# MKXdbV2_ModConn.net
KiCad netlist of a schematic drawn in Altium Designer
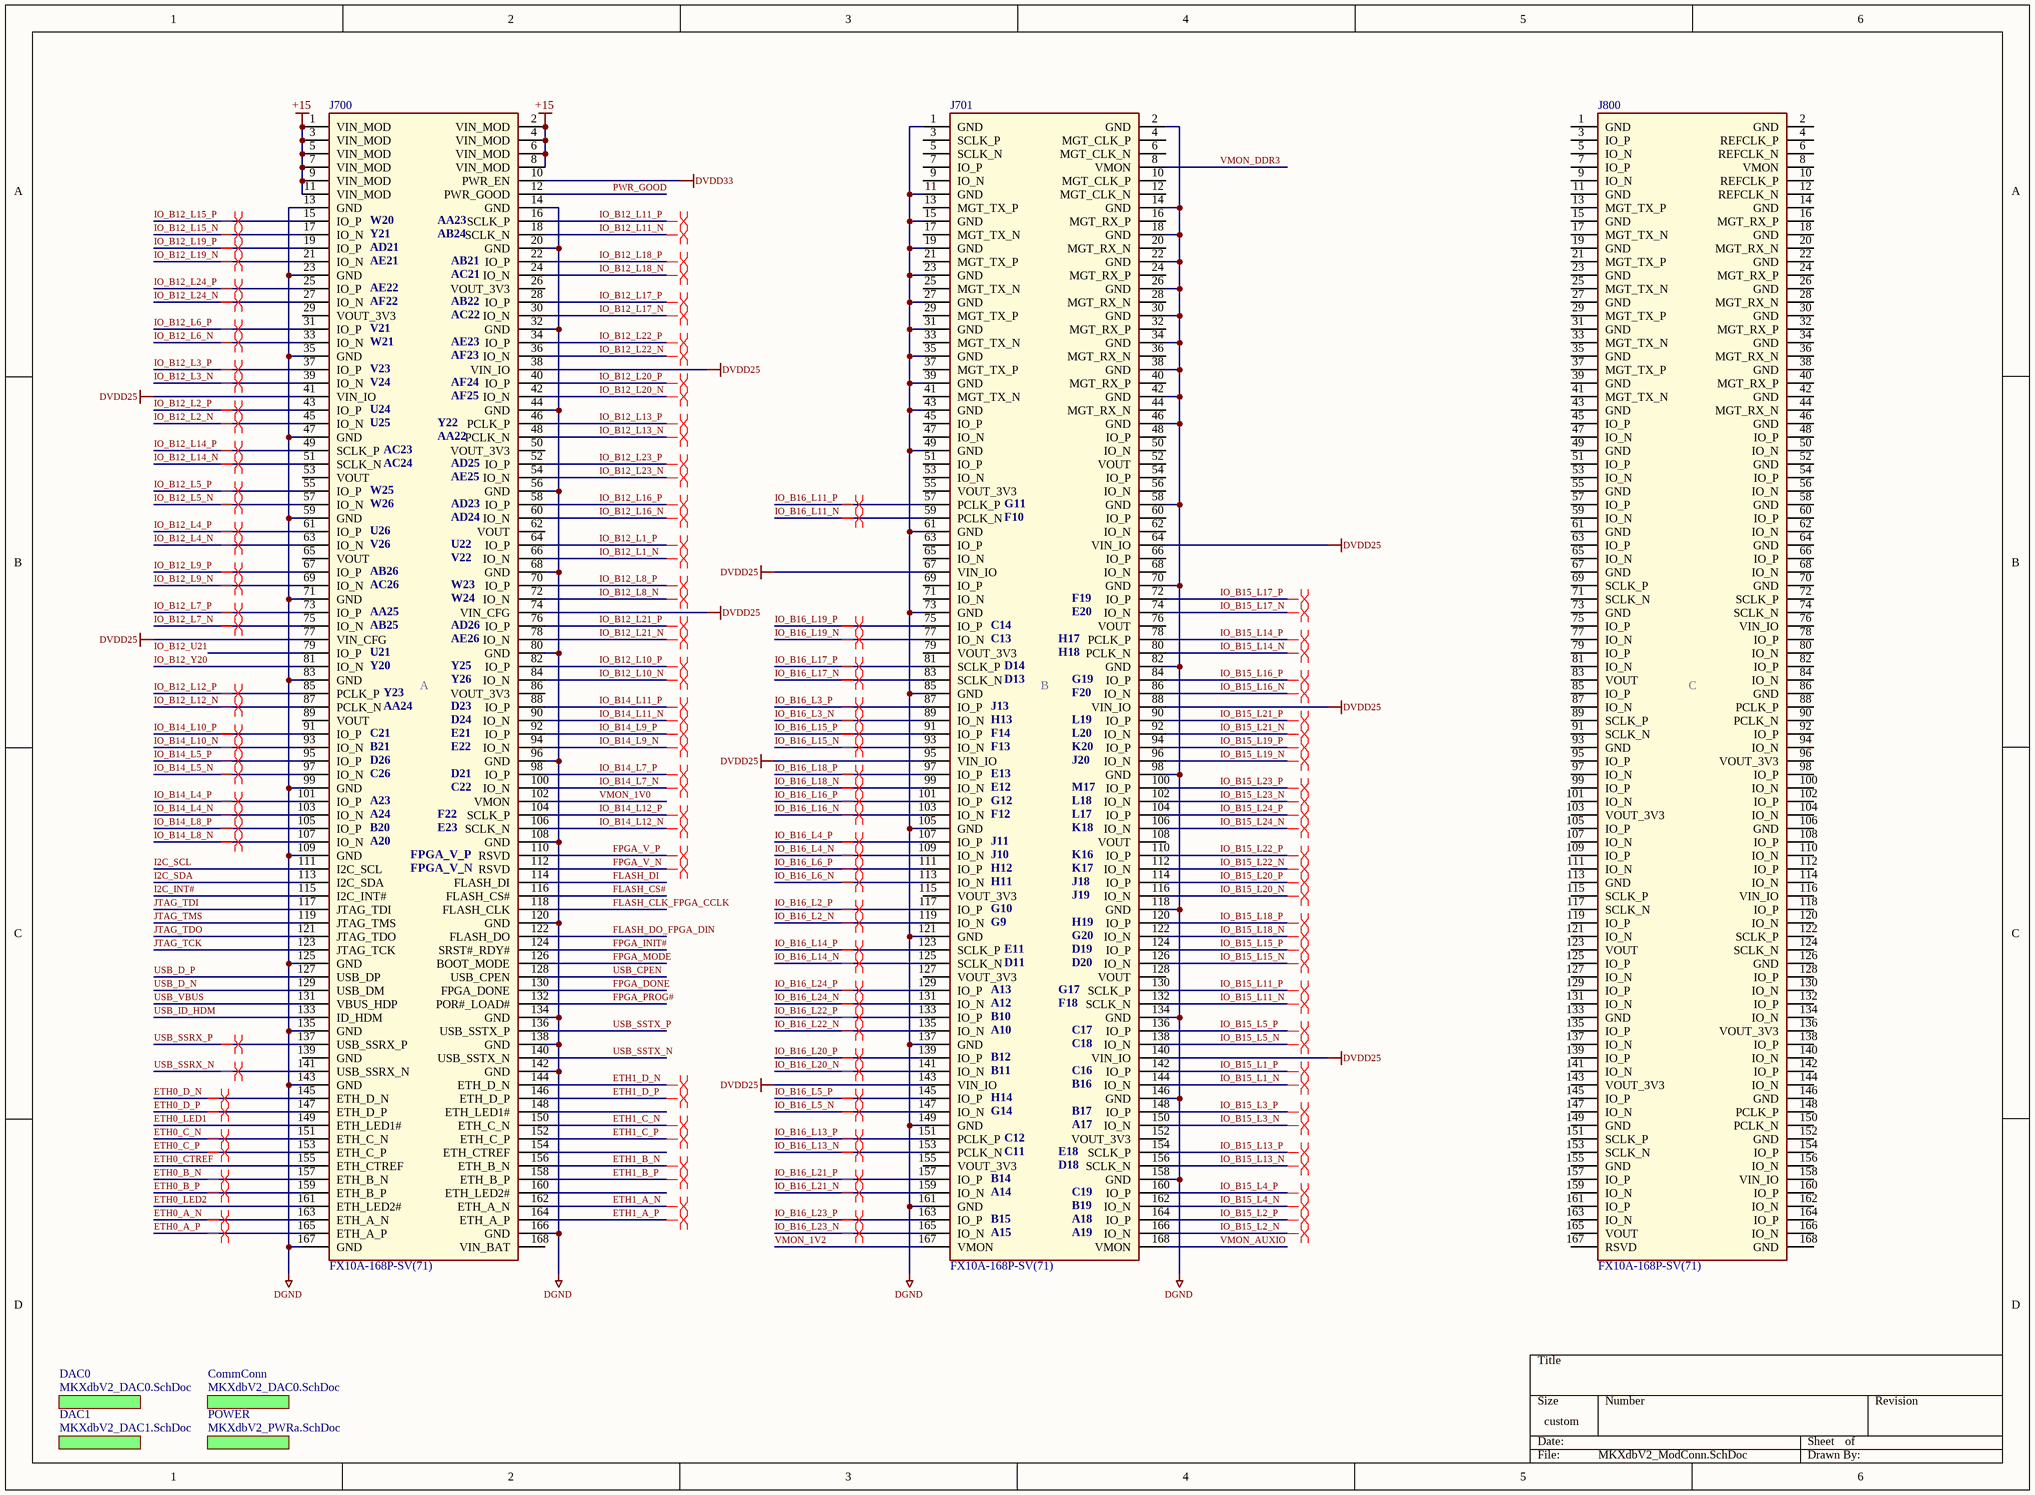
[diagram p0: MKXdbV2_ModConn.SchDoc]

(export (version "E")
  (design (tool "Eeschema 10.0.6"))
  (components
    (comp (ref "J700")
      (value "FX10A-168P-SV(71)")
      (footprint "Mercury_Baseboard_Connector")
      (description "Mercury Baseboard Connector")
      (fields
        (field (name "MANUFACTURER") "Hirose")
        (field (name "DISTPARTNUMBER") "FX10A-168P-SV(71)-ND")
        (field (name "CHECK SCH") "CG_2015-03-03")
      )
      (libsource (lib "Enclustra-Mars-Mercury-Altium-Library") (part "Mercury_Baseboard_Connector-A"))
    )
    (comp (ref "J701")
      (value "FX10A-168P-SV(71)")
      (footprint "Mercury_Baseboard_Connector")
      (description "Mercury Baseboard Connector")
      (fields
        (field (name "MANUFACTURER") "Hirose")
        (field (name "DISTPARTNUMBER") "FX10A-168P-SV(71)-ND")
        (field (name "CHECK SCH") "CG_2015-03-03")
      )
      (libsource (lib "Enclustra-Mars-Mercury-Altium-Library") (part "Mercury_Baseboard_Connector-B"))
    )
    (comp (ref "J800")
      (value "FX10A-168P-SV(71)")
      (footprint "Mercury_Baseboard_Connector")
      (description "Mercury Baseboard Connector")
      (fields
        (field (name "MANUFACTURER") "Hirose")
        (field (name "DISTPARTNUMBER") "FX10A-168P-SV(71)-ND")
        (field (name "CHECK SCH") "CG_2015-03-03")
      )
      (libsource (lib "Enclustra-Mars-Mercury-Altium-Library") (part "Mercury_Baseboard_Connector-C"))
    )
  )
  (nets
    (net (code "1") (name "+15") (class "Default")
      (node (ref "J700") (pin "1") (pinfunction "VIN_MOD_1") (pintype "power_in"))
      (node (ref "J700") (pin "11") (pinfunction "VIN_MOD_11") (pintype "power_in"))
      (node (ref "J700") (pin "2") (pinfunction "VIN_MOD_2") (pintype "power_in"))
      (node (ref "J700") (pin "3") (pinfunction "VIN_MOD_3") (pintype "power_in"))
      (node (ref "J700") (pin "4") (pinfunction "VIN_MOD_4") (pintype "power_in"))
      (node (ref "J700") (pin "5") (pinfunction "VIN_MOD_5") (pintype "power_in"))
      (node (ref "J700") (pin "6") (pinfunction "VIN_MOD_6") (pintype "power_in"))
      (node (ref "J700") (pin "7") (pinfunction "VIN_MOD_7") (pintype "power_in"))
      (node (ref "J700") (pin "8") (pinfunction "VIN_MOD_8") (pintype "power_in"))
      (node (ref "J700") (pin "9") (pinfunction "VIN_MOD_9") (pintype "power_in"))
    )
    (net (code "2") (name "/ETH0_A_N") (class "Default")
      (node (ref "J700") (pin "163") (pinfunction "ETH_A_N_163") (pintype "passive"))
    )
    (net (code "3") (name "/ETH0_A_P") (class "Default")
      (node (ref "J700") (pin "165") (pinfunction "ETH_A_P_165") (pintype "passive"))
    )
    (net (code "4") (name "/ETH0_B_N") (class "Default")
      (node (ref "J700") (pin "157") (pinfunction "ETH_B_N_157") (pintype "passive"))
    )
    (net (code "5") (name "/ETH0_B_P") (class "Default")
      (node (ref "J700") (pin "159") (pinfunction "ETH_B_P_159") (pintype "passive"))
    )
    (net (code "6") (name "/ETH0_CTREF") (class "Default")
      (node (ref "J700") (pin "155") (pinfunction "ETH_CTREF_155") (pintype "passive"))
    )
    (net (code "7") (name "/ETH0_C_N") (class "Default")
      (node (ref "J700") (pin "151") (pinfunction "ETH_C_N_151") (pintype "passive"))
    )
    (net (code "8") (name "/ETH0_C_P") (class "Default")
      (node (ref "J700") (pin "153") (pinfunction "ETH_C_P_153") (pintype "passive"))
    )
    (net (code "9") (name "/ETH0_D_N") (class "Default")
      (node (ref "J700") (pin "145") (pinfunction "ETH_D_N_145") (pintype "passive"))
    )
    (net (code "10") (name "/ETH0_D_P") (class "Default")
      (node (ref "J700") (pin "147") (pinfunction "ETH_D_P_147") (pintype "passive"))
    )
    (net (code "11") (name "/ETH0_LED1") (class "Default")
      (node (ref "J700") (pin "149") (pinfunction "ETH_LED1#_149") (pintype "passive"))
    )
    (net (code "12") (name "/ETH0_LED2") (class "Default")
      (node (ref "J700") (pin "161") (pinfunction "ETH_LED2#_161") (pintype "passive"))
    )
    (net (code "13") (name "/ETH1_A_N") (class "Default")
      (node (ref "J700") (pin "162") (pinfunction "ETH_A_N_162") (pintype "passive"))
    )
    (net (code "14") (name "/ETH1_A_P") (class "Default")
      (node (ref "J700") (pin "164") (pinfunction "ETH_A_P_164") (pintype "passive"))
    )
    (net (code "15") (name "/ETH1_B_N") (class "Default")
      (node (ref "J700") (pin "156") (pinfunction "ETH_B_N_156") (pintype "passive"))
    )
    (net (code "16") (name "/ETH1_B_P") (class "Default")
      (node (ref "J700") (pin "158") (pinfunction "ETH_B_P_158") (pintype "passive"))
    )
    (net (code "17") (name "/ETH1_C_N") (class "Default")
      (node (ref "J700") (pin "150") (pinfunction "ETH_C_N_150") (pintype "passive"))
    )
    (net (code "18") (name "/ETH1_C_P") (class "Default")
      (node (ref "J700") (pin "152") (pinfunction "ETH_C_P_152") (pintype "passive"))
    )
    (net (code "19") (name "/ETH1_D_N") (class "Default")
      (node (ref "J700") (pin "144") (pinfunction "ETH_D_N_144") (pintype "passive"))
    )
    (net (code "20") (name "/ETH1_D_P") (class "Default")
      (node (ref "J700") (pin "146") (pinfunction "ETH_D_P_146") (pintype "passive"))
    )
    (net (code "21") (name "/FLASH_CLK_FPGA_CCLK") (class "Default")
      (node (ref "J700") (pin "118") (pinfunction "FLASH_CLK_118") (pintype "passive"))
    )
    (net (code "22") (name "/FLASH_CS#") (class "Default")
      (node (ref "J700") (pin "116") (pinfunction "FLASH_CS#_116") (pintype "passive"))
    )
    (net (code "23") (name "/FLASH_DI") (class "Default")
      (node (ref "J700") (pin "114") (pinfunction "FLASH_DI_114") (pintype "passive"))
    )
    (net (code "24") (name "/FLASH_DO_FPGA_DIN") (class "Default")
      (node (ref "J700") (pin "122") (pinfunction "FLASH_DO_122") (pintype "passive"))
    )
    (net (code "25") (name "/FPGA_DONE") (class "Default")
      (node (ref "J700") (pin "130") (pinfunction "FPGA_DONE_130") (pintype "passive"))
    )
    (net (code "26") (name "/FPGA_INIT#") (class "Default")
      (node (ref "J700") (pin "124") (pinfunction "SRST#_RDY#_124") (pintype "passive"))
    )
    (net (code "27") (name "/FPGA_MODE") (class "Default")
      (node (ref "J700") (pin "126") (pinfunction "BOOT_MODE_126") (pintype "passive"))
    )
    (net (code "28") (name "/FPGA_PROG#") (class "Default")
      (node (ref "J700") (pin "132") (pinfunction "POR#_LOAD#_132") (pintype "passive"))
    )
    (net (code "29") (name "/FPGA_V_N") (class "Default")
      (node (ref "J700") (pin "112") (pinfunction "RSVD_112") (pintype "passive"))
    )
    (net (code "30") (name "/FPGA_V_P") (class "Default")
      (node (ref "J700") (pin "110") (pinfunction "RSVD_110") (pintype "passive"))
    )
    (net (code "31") (name "/I2C_INT#") (class "Default")
      (node (ref "J700") (pin "115") (pinfunction "I2C_INT#_115") (pintype "passive"))
    )
    (net (code "32") (name "/I2C_SCL") (class "Default")
      (node (ref "J700") (pin "111") (pinfunction "I2C_SCL_111") (pintype "passive"))
    )
    (net (code "33") (name "/I2C_SDA") (class "Default")
      (node (ref "J700") (pin "113") (pinfunction "I2C_SDA_113") (pintype "passive"))
    )
    (net (code "34") (name "/IO_B12_L1_N") (class "Default")
      (node (ref "J700") (pin "66") (pinfunction "IO_N_66") (pintype "passive"))
    )
    (net (code "35") (name "/IO_B12_L1_P") (class "Default")
      (node (ref "J700") (pin "64") (pinfunction "IO_P_64") (pintype "passive"))
    )
    (net (code "36") (name "/IO_B12_L2_N") (class "Default")
      (node (ref "J700") (pin "45") (pinfunction "IO_N_45") (pintype "passive"))
    )
    (net (code "37") (name "/IO_B12_L2_P") (class "Default")
      (node (ref "J700") (pin "43") (pinfunction "IO_P_43") (pintype "passive"))
    )
    (net (code "38") (name "/IO_B12_L3_N") (class "Default")
      (node (ref "J700") (pin "39") (pinfunction "IO_N_39") (pintype "passive"))
    )
    (net (code "39") (name "/IO_B12_L3_P") (class "Default")
      (node (ref "J700") (pin "37") (pinfunction "IO_P_37") (pintype "passive"))
    )
    (net (code "40") (name "/IO_B12_L4_N") (class "Default")
      (node (ref "J700") (pin "63") (pinfunction "IO_N_63") (pintype "passive"))
    )
    (net (code "41") (name "/IO_B12_L4_P") (class "Default")
      (node (ref "J700") (pin "61") (pinfunction "IO_P_61") (pintype "passive"))
    )
    (net (code "42") (name "/IO_B12_L5_N") (class "Default")
      (node (ref "J700") (pin "57") (pinfunction "IO_N_57") (pintype "passive"))
    )
    (net (code "43") (name "/IO_B12_L5_P") (class "Default")
      (node (ref "J700") (pin "55") (pinfunction "IO_P_55") (pintype "passive"))
    )
    (net (code "44") (name "/IO_B12_L6_N") (class "Default")
      (node (ref "J700") (pin "33") (pinfunction "IO_N_33") (pintype "passive"))
    )
    (net (code "45") (name "/IO_B12_L6_P") (class "Default")
      (node (ref "J700") (pin "31") (pinfunction "IO_P_31") (pintype "passive"))
    )
    (net (code "46") (name "/IO_B12_L7_N") (class "Default")
      (node (ref "J700") (pin "75") (pinfunction "IO_N_75") (pintype "passive"))
    )
    (net (code "47") (name "/IO_B12_L7_P") (class "Default")
      (node (ref "J700") (pin "73") (pinfunction "IO_P_73") (pintype "passive"))
    )
    (net (code "48") (name "/IO_B12_L8_N") (class "Default")
      (node (ref "J700") (pin "72") (pinfunction "IO_N_72") (pintype "passive"))
    )
    (net (code "49") (name "/IO_B12_L8_P") (class "Default")
      (node (ref "J700") (pin "70") (pinfunction "IO_P_70") (pintype "passive"))
    )
    (net (code "50") (name "/IO_B12_L9_N") (class "Default")
      (node (ref "J700") (pin "69") (pinfunction "IO_N_69") (pintype "passive"))
    )
    (net (code "51") (name "/IO_B12_L9_P") (class "Default")
      (node (ref "J700") (pin "67") (pinfunction "IO_P_67") (pintype "passive"))
    )
    (net (code "52") (name "/IO_B12_L10_N") (class "Default")
      (node (ref "J700") (pin "84") (pinfunction "IO_N_84") (pintype "passive"))
    )
    (net (code "53") (name "/IO_B12_L10_P") (class "Default")
      (node (ref "J700") (pin "82") (pinfunction "IO_P_82") (pintype "passive"))
    )
    (net (code "54") (name "/IO_B12_L11_N") (class "Default")
      (node (ref "J700") (pin "18") (pinfunction "SCLK_N_18") (pintype "passive"))
    )
    (net (code "55") (name "/IO_B12_L11_P") (class "Default")
      (node (ref "J700") (pin "16") (pinfunction "SCLK_P_16") (pintype "passive"))
    )
    (net (code "56") (name "/IO_B12_L12_N") (class "Default")
      (node (ref "J700") (pin "87") (pinfunction "PCLK_N_87") (pintype "passive"))
    )
    (net (code "57") (name "/IO_B12_L12_P") (class "Default")
      (node (ref "J700") (pin "85") (pinfunction "PCLK_P_85") (pintype "passive"))
    )
    (net (code "58") (name "/IO_B12_L13_N") (class "Default")
      (node (ref "J700") (pin "48") (pinfunction "PCLK_N_48") (pintype "passive"))
    )
    (net (code "59") (name "/IO_B12_L13_P") (class "Default")
      (node (ref "J700") (pin "46") (pinfunction "PCLK_P_46") (pintype "passive"))
    )
    (net (code "60") (name "/IO_B12_L14_N") (class "Default")
      (node (ref "J700") (pin "51") (pinfunction "SCLK_N_51") (pintype "passive"))
    )
    (net (code "61") (name "/IO_B12_L14_P") (class "Default")
      (node (ref "J700") (pin "49") (pinfunction "SCLK_P_49") (pintype "passive"))
    )
    (net (code "62") (name "/IO_B12_L15_N") (class "Default")
      (node (ref "J700") (pin "17") (pinfunction "IO_N_17") (pintype "passive"))
    )
    (net (code "63") (name "/IO_B12_L15_P") (class "Default")
      (node (ref "J700") (pin "15") (pinfunction "IO_P_15") (pintype "passive"))
    )
    (net (code "64") (name "/IO_B12_L16_N") (class "Default")
      (node (ref "J700") (pin "60") (pinfunction "IO_N_60") (pintype "passive"))
    )
    (net (code "65") (name "/IO_B12_L16_P") (class "Default")
      (node (ref "J700") (pin "58") (pinfunction "IO_P_58") (pintype "passive"))
    )
    (net (code "66") (name "/IO_B12_L17_N") (class "Default")
      (node (ref "J700") (pin "30") (pinfunction "IO_N_30") (pintype "passive"))
    )
    (net (code "67") (name "/IO_B12_L17_P") (class "Default")
      (node (ref "J700") (pin "28") (pinfunction "IO_P_28") (pintype "passive"))
    )
    (net (code "68") (name "/IO_B12_L18_N") (class "Default")
      (node (ref "J700") (pin "24") (pinfunction "IO_N_24") (pintype "passive"))
    )
    (net (code "69") (name "/IO_B12_L18_P") (class "Default")
      (node (ref "J700") (pin "22") (pinfunction "IO_P_22") (pintype "passive"))
    )
    (net (code "70") (name "/IO_B12_L19_N") (class "Default")
      (node (ref "J700") (pin "21") (pinfunction "IO_N_21") (pintype "passive"))
    )
    (net (code "71") (name "/IO_B12_L19_P") (class "Default")
      (node (ref "J700") (pin "19") (pinfunction "IO_P_19") (pintype "passive"))
    )
    (net (code "72") (name "/IO_B12_L20_N") (class "Default")
      (node (ref "J700") (pin "42") (pinfunction "IO_N_42") (pintype "passive"))
    )
    (net (code "73") (name "/IO_B12_L20_P") (class "Default")
      (node (ref "J700") (pin "40") (pinfunction "IO_P_40") (pintype "passive"))
    )
    (net (code "74") (name "/IO_B12_L21_N") (class "Default")
      (node (ref "J700") (pin "78") (pinfunction "IO_N_78") (pintype "passive"))
    )
    (net (code "75") (name "/IO_B12_L21_P") (class "Default")
      (node (ref "J700") (pin "76") (pinfunction "IO_P_76") (pintype "passive"))
    )
    (net (code "76") (name "/IO_B12_L22_N") (class "Default")
      (node (ref "J700") (pin "36") (pinfunction "IO_N_36") (pintype "passive"))
    )
    (net (code "77") (name "/IO_B12_L22_P") (class "Default")
      (node (ref "J700") (pin "34") (pinfunction "IO_P_34") (pintype "passive"))
    )
    (net (code "78") (name "/IO_B12_L23_N") (class "Default")
      (node (ref "J700") (pin "54") (pinfunction "IO_N_54") (pintype "passive"))
    )
    (net (code "79") (name "/IO_B12_L23_P") (class "Default")
      (node (ref "J700") (pin "52") (pinfunction "IO_P_52") (pintype "passive"))
    )
    (net (code "80") (name "/IO_B12_L24_N") (class "Default")
      (node (ref "J700") (pin "27") (pinfunction "IO_N_27") (pintype "passive"))
    )
    (net (code "81") (name "/IO_B12_L24_P") (class "Default")
      (node (ref "J700") (pin "25") (pinfunction "IO_P_25") (pintype "passive"))
    )
    (net (code "83") (name "/IO_B12_Y20") (class "Default")
      (node (ref "J700") (pin "81") (pinfunction "IO_N_81") (pintype "passive"))
    )
    (net (code "84") (name "/IO_B14_L4_N") (class "Default")
      (node (ref "J700") (pin "103") (pinfunction "IO_N_103") (pintype "passive"))
    )
    (net (code "85") (name "/IO_B14_L4_P") (class "Default")
      (node (ref "J700") (pin "101") (pinfunction "IO_P_101") (pintype "passive"))
    )
    (net (code "86") (name "/IO_B14_L5_N") (class "Default")
      (node (ref "J700") (pin "97") (pinfunction "IO_N_97") (pintype "passive"))
    )
    (net (code "87") (name "/IO_B14_L5_P") (class "Default")
      (node (ref "J700") (pin "95") (pinfunction "IO_P_95") (pintype "passive"))
    )
    (net (code "88") (name "/IO_B14_L7_N") (class "Default")
      (node (ref "J700") (pin "100") (pinfunction "IO_N_100") (pintype "passive"))
    )
    (net (code "89") (name "/IO_B14_L7_P") (class "Default")
      (node (ref "J700") (pin "98") (pinfunction "IO_P_98") (pintype "passive"))
    )
    (net (code "90") (name "/IO_B14_L8_N") (class "Default")
      (node (ref "J700") (pin "107") (pinfunction "IO_N_107") (pintype "passive"))
    )
    (net (code "91") (name "/IO_B14_L8_P") (class "Default")
      (node (ref "J700") (pin "105") (pinfunction "IO_P_105") (pintype "passive"))
    )
    (net (code "92") (name "/IO_B14_L9_N") (class "Default")
      (node (ref "J700") (pin "94") (pinfunction "IO_N_94") (pintype "passive"))
    )
    (net (code "93") (name "/IO_B14_L9_P") (class "Default")
      (node (ref "J700") (pin "92") (pinfunction "IO_P_92") (pintype "passive"))
    )
    (net (code "94") (name "/IO_B14_L10_N") (class "Default")
      (node (ref "J700") (pin "93") (pinfunction "IO_N_93") (pintype "passive"))
    )
    (net (code "95") (name "/IO_B14_L10_P") (class "Default")
      (node (ref "J700") (pin "91") (pinfunction "IO_P_91") (pintype "passive"))
    )
    (net (code "96") (name "/IO_B14_L11_N") (class "Default")
      (node (ref "J700") (pin "90") (pinfunction "IO_N_90") (pintype "passive"))
    )
    (net (code "97") (name "/IO_B14_L11_P") (class "Default")
      (node (ref "J700") (pin "88") (pinfunction "IO_P_88") (pintype "passive"))
    )
    (net (code "98") (name "/IO_B14_L12_N") (class "Default")
      (node (ref "J700") (pin "106") (pinfunction "SCLK_N_106") (pintype "passive"))
    )
    (net (code "99") (name "/IO_B14_L12_P") (class "Default")
      (node (ref "J700") (pin "104") (pinfunction "SCLK_P_104") (pintype "passive"))
    )
    (net (code "100") (name "/IO_B15_L1_N") (class "Default")
      (node (ref "J701") (pin "144") (pinfunction "IO_N_144") (pintype "passive"))
    )
    (net (code "101") (name "/IO_B15_L1_P") (class "Default")
      (node (ref "J701") (pin "142") (pinfunction "IO_P_142") (pintype "passive"))
    )
    (net (code "102") (name "/IO_B15_L2_N") (class "Default")
      (node (ref "J701") (pin "166") (pinfunction "IO_N_166") (pintype "passive"))
    )
    (net (code "103") (name "/IO_B15_L2_P") (class "Default")
      (node (ref "J701") (pin "164") (pinfunction "IO_P_164") (pintype "passive"))
    )
    (net (code "104") (name "/IO_B15_L3_N") (class "Default")
      (node (ref "J701") (pin "150") (pinfunction "IO_N_150") (pintype "passive"))
    )
    (net (code "105") (name "/IO_B15_L3_P") (class "Default")
      (node (ref "J701") (pin "148") (pinfunction "IO_P_148") (pintype "passive"))
    )
    (net (code "106") (name "/IO_B15_L4_N") (class "Default")
      (node (ref "J701") (pin "162") (pinfunction "IO_N_162") (pintype "passive"))
    )
    (net (code "107") (name "/IO_B15_L4_P") (class "Default")
      (node (ref "J701") (pin "160") (pinfunction "IO_P_160") (pintype "passive"))
    )
    (net (code "108") (name "/IO_B15_L5_N") (class "Default")
      (node (ref "J701") (pin "138") (pinfunction "IO_N_138") (pintype "passive"))
    )
    (net (code "109") (name "/IO_B15_L5_P") (class "Default")
      (node (ref "J701") (pin "136") (pinfunction "IO_P_136") (pintype "passive"))
    )
    (net (code "110") (name "/IO_B15_L11_N") (class "Default")
      (node (ref "J701") (pin "132") (pinfunction "SCLK_N_132") (pintype "passive"))
    )
    (net (code "111") (name "/IO_B15_L11_P") (class "Default")
      (node (ref "J701") (pin "130") (pinfunction "SCLK_P_130") (pintype "passive"))
    )
    (net (code "112") (name "/IO_B15_L13_N") (class "Default")
      (node (ref "J701") (pin "156") (pinfunction "SCLK_N_156") (pintype "passive"))
    )
    (net (code "113") (name "/IO_B15_L13_P") (class "Default")
      (node (ref "J701") (pin "154") (pinfunction "SCLK_P_154") (pintype "passive"))
    )
    (net (code "114") (name "/IO_B15_L14_N") (class "Default")
      (node (ref "J701") (pin "80") (pinfunction "PCLK_N_80") (pintype "passive"))
    )
    (net (code "115") (name "/IO_B15_L14_P") (class "Default")
      (node (ref "J701") (pin "78") (pinfunction "PCLK_P_78") (pintype "passive"))
    )
    (net (code "116") (name "/IO_B15_L15_N") (class "Default")
      (node (ref "J701") (pin "126") (pinfunction "IO_N_126") (pintype "passive"))
    )
    (net (code "117") (name "/IO_B15_L15_P") (class "Default")
      (node (ref "J701") (pin "124") (pinfunction "IO_P_124") (pintype "passive"))
    )
    (net (code "118") (name "/IO_B15_L16_N") (class "Default")
      (node (ref "J701") (pin "86") (pinfunction "IO_N_86") (pintype "passive"))
    )
    (net (code "119") (name "/IO_B15_L16_P") (class "Default")
      (node (ref "J701") (pin "84") (pinfunction "IO_P_84") (pintype "passive"))
    )
    (net (code "120") (name "/IO_B15_L17_N") (class "Default")
      (node (ref "J701") (pin "74") (pinfunction "IO_N_74") (pintype "passive"))
    )
    (net (code "121") (name "/IO_B15_L17_P") (class "Default")
      (node (ref "J701") (pin "72") (pinfunction "IO_P_72") (pintype "passive"))
    )
    (net (code "122") (name "/IO_B15_L18_N") (class "Default")
      (node (ref "J701") (pin "122") (pinfunction "IO_N_122") (pintype "passive"))
    )
    (net (code "123") (name "/IO_B15_L18_P") (class "Default")
      (node (ref "J701") (pin "120") (pinfunction "IO_P_120") (pintype "passive"))
    )
    (net (code "124") (name "/IO_B15_L19_N") (class "Default")
      (node (ref "J701") (pin "96") (pinfunction "IO_N_96") (pintype "passive"))
    )
    (net (code "125") (name "/IO_B15_L19_P") (class "Default")
      (node (ref "J701") (pin "94") (pinfunction "IO_P_94") (pintype "passive"))
    )
    (net (code "126") (name "/IO_B15_L20_N") (class "Default")
      (node (ref "J701") (pin "116") (pinfunction "IO_N_116") (pintype "passive"))
    )
    (net (code "127") (name "/IO_B15_L20_P") (class "Default")
      (node (ref "J701") (pin "114") (pinfunction "IO_P_114") (pintype "passive"))
    )
    (net (code "128") (name "/IO_B15_L21_N") (class "Default")
      (node (ref "J701") (pin "92") (pinfunction "IO_N_92") (pintype "passive"))
    )
    (net (code "129") (name "/IO_B15_L21_P") (class "Default")
      (node (ref "J701") (pin "90") (pinfunction "IO_P_90") (pintype "passive"))
    )
    (net (code "130") (name "/IO_B15_L22_N") (class "Default")
      (node (ref "J701") (pin "112") (pinfunction "IO_N_112") (pintype "passive"))
    )
    (net (code "131") (name "/IO_B15_L22_P") (class "Default")
      (node (ref "J701") (pin "110") (pinfunction "IO_P_110") (pintype "passive"))
    )
    (net (code "132") (name "/IO_B15_L23_N") (class "Default")
      (node (ref "J701") (pin "102") (pinfunction "IO_N_102") (pintype "passive"))
    )
    (net (code "133") (name "/IO_B15_L23_P") (class "Default")
      (node (ref "J701") (pin "100") (pinfunction "IO_P_100") (pintype "passive"))
    )
    (net (code "134") (name "/IO_B15_L24_N") (class "Default")
      (node (ref "J701") (pin "106") (pinfunction "IO_N_106") (pintype "passive"))
    )
    (net (code "135") (name "/IO_B15_L24_P") (class "Default")
      (node (ref "J701") (pin "104") (pinfunction "IO_P_104") (pintype "passive"))
    )
    (net (code "136") (name "/IO_B16_L2_N") (class "Default")
      (node (ref "J701") (pin "119") (pinfunction "IO_N_119") (pintype "passive"))
    )
    (net (code "137") (name "/IO_B16_L2_P") (class "Default")
      (node (ref "J701") (pin "117") (pinfunction "IO_P_117") (pintype "passive"))
    )
    (net (code "138") (name "/IO_B16_L3_N") (class "Default")
      (node (ref "J701") (pin "89") (pinfunction "IO_N_89") (pintype "passive"))
    )
    (net (code "139") (name "/IO_B16_L3_P") (class "Default")
      (node (ref "J701") (pin "87") (pinfunction "IO_P_87") (pintype "passive"))
    )
    (net (code "140") (name "/IO_B16_L4_N") (class "Default")
      (node (ref "J701") (pin "109") (pinfunction "IO_N_109") (pintype "passive"))
    )
    (net (code "141") (name "/IO_B16_L4_P") (class "Default")
      (node (ref "J701") (pin "107") (pinfunction "IO_P_107") (pintype "passive"))
    )
    (net (code "142") (name "/IO_B16_L5_N") (class "Default")
      (node (ref "J701") (pin "147") (pinfunction "IO_N_147") (pintype "passive"))
    )
    (net (code "143") (name "/IO_B16_L5_P") (class "Default")
      (node (ref "J701") (pin "145") (pinfunction "IO_P_145") (pintype "passive"))
    )
    (net (code "144") (name "/IO_B16_L6_N") (class "Default")
      (node (ref "J701") (pin "113") (pinfunction "IO_N_113") (pintype "passive"))
    )
    (net (code "145") (name "/IO_B16_L6_P") (class "Default")
      (node (ref "J701") (pin "111") (pinfunction "IO_P_111") (pintype "passive"))
    )
    (net (code "146") (name "/IO_B16_L11_N") (class "Default")
      (node (ref "J701") (pin "59") (pinfunction "PCLK_N_59") (pintype "passive"))
    )
    (net (code "147") (name "/IO_B16_L11_P") (class "Default")
      (node (ref "J701") (pin "57") (pinfunction "PCLK_P_57") (pintype "passive"))
    )
    (net (code "148") (name "/IO_B16_L13_N") (class "Default")
      (node (ref "J701") (pin "153") (pinfunction "PCLK_N_153") (pintype "passive"))
    )
    (net (code "149") (name "/IO_B16_L13_P") (class "Default")
      (node (ref "J701") (pin "151") (pinfunction "PCLK_P_151") (pintype "passive"))
    )
    (net (code "150") (name "/IO_B16_L14_N") (class "Default")
      (node (ref "J701") (pin "125") (pinfunction "SCLK_N_125") (pintype "passive"))
    )
    (net (code "151") (name "/IO_B16_L14_P") (class "Default")
      (node (ref "J701") (pin "123") (pinfunction "SCLK_P_123") (pintype "passive"))
    )
    (net (code "152") (name "/IO_B16_L15_N") (class "Default")
      (node (ref "J701") (pin "93") (pinfunction "IO_N_93") (pintype "passive"))
    )
    (net (code "153") (name "/IO_B16_L15_P") (class "Default")
      (node (ref "J701") (pin "91") (pinfunction "IO_P_91") (pintype "passive"))
    )
    (net (code "154") (name "/IO_B16_L16_N") (class "Default")
      (node (ref "J701") (pin "103") (pinfunction "IO_N_103") (pintype "passive"))
    )
    (net (code "155") (name "/IO_B16_L16_P") (class "Default")
      (node (ref "J701") (pin "101") (pinfunction "IO_P_101") (pintype "passive"))
    )
    (net (code "156") (name "/IO_B16_L17_N") (class "Default")
      (node (ref "J701") (pin "83") (pinfunction "SCLK_N_83") (pintype "passive"))
    )
    (net (code "157") (name "/IO_B16_L17_P") (class "Default")
      (node (ref "J701") (pin "81") (pinfunction "SCLK_P_81") (pintype "passive"))
    )
    (net (code "158") (name "/IO_B16_L18_N") (class "Default")
      (node (ref "J701") (pin "99") (pinfunction "IO_N_99") (pintype "passive"))
    )
    (net (code "159") (name "/IO_B16_L18_P") (class "Default")
      (node (ref "J701") (pin "97") (pinfunction "IO_P_97") (pintype "passive"))
    )
    (net (code "160") (name "/IO_B16_L19_N") (class "Default")
      (node (ref "J701") (pin "77") (pinfunction "IO_N_77") (pintype "passive"))
    )
    (net (code "161") (name "/IO_B16_L19_P") (class "Default")
      (node (ref "J701") (pin "75") (pinfunction "IO_P_75") (pintype "passive"))
    )
    (net (code "162") (name "/IO_B16_L20_N") (class "Default")
      (node (ref "J701") (pin "141") (pinfunction "IO_N_141") (pintype "passive"))
    )
    (net (code "163") (name "/IO_B16_L20_P") (class "Default")
      (node (ref "J701") (pin "139") (pinfunction "IO_P_139") (pintype "passive"))
    )
    (net (code "164") (name "/IO_B16_L21_N") (class "Default")
      (node (ref "J701") (pin "159") (pinfunction "IO_N_159") (pintype "passive"))
    )
    (net (code "165") (name "/IO_B16_L21_P") (class "Default")
      (node (ref "J701") (pin "157") (pinfunction "IO_P_157") (pintype "passive"))
    )
    (net (code "166") (name "/IO_B16_L22_N") (class "Default")
      (node (ref "J701") (pin "135") (pinfunction "IO_N_135") (pintype "passive"))
    )
    (net (code "167") (name "/IO_B16_L22_P") (class "Default")
      (node (ref "J701") (pin "133") (pinfunction "IO_P_133") (pintype "passive"))
    )
    (net (code "168") (name "/IO_B16_L23_N") (class "Default")
      (node (ref "J701") (pin "165") (pinfunction "IO_N_165") (pintype "passive"))
    )
    (net (code "169") (name "/IO_B16_L23_P") (class "Default")
      (node (ref "J701") (pin "163") (pinfunction "IO_P_163") (pintype "passive"))
    )
    (net (code "170") (name "/IO_B16_L24_N") (class "Default")
      (node (ref "J701") (pin "131") (pinfunction "IO_N_131") (pintype "passive"))
    )
    (net (code "171") (name "/IO_B16_L24_P") (class "Default")
      (node (ref "J701") (pin "129") (pinfunction "IO_P_129") (pintype "passive"))
    )
    (net (code "172") (name "/JTAG_TCK") (class "Default")
      (node (ref "J700") (pin "123") (pinfunction "JTAG_TCK_123") (pintype "passive"))
    )
    (net (code "173") (name "/JTAG_TDI") (class "Default")
      (node (ref "J700") (pin "117") (pinfunction "JTAG_TDI_117") (pintype "passive"))
    )
    (net (code "174") (name "/JTAG_TDO") (class "Default")
      (node (ref "J700") (pin "121") (pinfunction "JTAG_TDO_121") (pintype "passive"))
    )
    (net (code "175") (name "/JTAG_TMS") (class "Default")
      (node (ref "J700") (pin "119") (pinfunction "JTAG_TMS_119") (pintype "passive"))
    )
    (net (code "176") (name "/PWR_GOOD") (class "Default")
      (node (ref "J700") (pin "12") (pinfunction "PWR_GOOD_12") (pintype "passive"))
    )
    (net (code "177") (name "/USB_CPEN") (class "Default")
      (node (ref "J700") (pin "128") (pinfunction "USB_CPEN_128") (pintype "passive"))
    )
    (net (code "178") (name "/USB_D_N") (class "Default")
      (node (ref "J700") (pin "129") (pinfunction "USB_DM_129") (pintype "passive"))
    )
    (net (code "179") (name "/USB_D_P") (class "Default")
      (node (ref "J700") (pin "127") (pinfunction "USB_DP_127") (pintype "passive"))
    )
    (net (code "180") (name "/USB_ID_HDM") (class "Default")
      (node (ref "J700") (pin "133") (pinfunction "ID_HDM_133") (pintype "passive"))
    )
    (net (code "181") (name "/USB_SSRX_N") (class "Default")
      (node (ref "J700") (pin "141") (pinfunction "USB_SSRX_N_141") (pintype "passive"))
    )
    (net (code "182") (name "/USB_SSRX_P") (class "Default")
      (node (ref "J700") (pin "137") (pinfunction "USB_SSRX_P_137") (pintype "passive"))
    )
    (net (code "183") (name "/USB_SSTX_N") (class "Default")
      (node (ref "J700") (pin "140") (pinfunction "USB_SSTX_N_140") (pintype "passive"))
    )
    (net (code "184") (name "/USB_SSTX_P") (class "Default")
      (node (ref "J700") (pin "136") (pinfunction "USB_SSTX_P_136") (pintype "passive"))
    )
    (net (code "185") (name "/USB_VBUS") (class "Default")
      (node (ref "J700") (pin "131") (pinfunction "VBUS_HDP_131") (pintype "passive"))
    )
    (net (code "186") (name "/VMON_1V0") (class "Default")
      (node (ref "J700") (pin "102") (pinfunction "VMON_102") (pintype "passive"))
    )
    (net (code "187") (name "/VMON_1V2") (class "Default")
      (node (ref "J701") (pin "167") (pinfunction "VMON_167") (pintype "passive"))
    )
    (net (code "188") (name "/VMON_AUXIO") (class "Default")
      (node (ref "J701") (pin "168") (pinfunction "VMON_168") (pintype "passive"))
    )
    (net (code "189") (name "/VMON_DDR3") (class "Default")
      (node (ref "J701") (pin "8") (pinfunction "VMON_8") (pintype "passive"))
    )
    (net (code "190") (name "DGND") (class "Default")
      (node (ref "J700") (pin "108") (pinfunction "GND_108") (pintype "power_in"))
      (node (ref "J700") (pin "109") (pinfunction "GND_109") (pintype "power_in"))
      (node (ref "J700") (pin "120") (pinfunction "GND_120") (pintype "power_in"))
      (node (ref "J700") (pin "125") (pinfunction "GND_125") (pintype "power_in"))
      (node (ref "J700") (pin "13") (pinfunction "GND_13") (pintype "power_in"))
      (node (ref "J700") (pin "134") (pinfunction "GND_134") (pintype "power_in"))
      (node (ref "J700") (pin "135") (pinfunction "GND_135") (pintype "power_in"))
      (node (ref "J700") (pin "138") (pinfunction "GND_138") (pintype "power_in"))
      (node (ref "J700") (pin "14") (pinfunction "GND_14") (pintype "power_in"))
      (node (ref "J700") (pin "142") (pinfunction "GND_142") (pintype "power_in"))
      (node (ref "J700") (pin "143") (pinfunction "GND_143") (pintype "power_in"))
      (node (ref "J700") (pin "166") (pinfunction "GND_166") (pintype "power_in"))
      (node (ref "J700") (pin "167") (pinfunction "GND_167") (pintype "power_in"))
      (node (ref "J700") (pin "20") (pinfunction "GND_20") (pintype "power_in"))
      (node (ref "J700") (pin "23") (pinfunction "GND_23") (pintype "power_in"))
      (node (ref "J700") (pin "32") (pinfunction "GND_32") (pintype "power_in"))
      (node (ref "J700") (pin "35") (pinfunction "GND_35") (pintype "power_in"))
      (node (ref "J700") (pin "44") (pinfunction "GND_44") (pintype "power_in"))
      (node (ref "J700") (pin "47") (pinfunction "GND_47") (pintype "power_in"))
      (node (ref "J700") (pin "56") (pinfunction "GND_56") (pintype "power_in"))
      (node (ref "J700") (pin "59") (pinfunction "GND_59") (pintype "power_in"))
      (node (ref "J700") (pin "68") (pinfunction "GND_68") (pintype "power_in"))
      (node (ref "J700") (pin "71") (pinfunction "GND_71") (pintype "power_in"))
      (node (ref "J700") (pin "80") (pinfunction "GND_80") (pintype "power_in"))
      (node (ref "J700") (pin "83") (pinfunction "GND_83") (pintype "power_in"))
      (node (ref "J700") (pin "96") (pinfunction "GND_96") (pintype "power_in"))
      (node (ref "J700") (pin "99") (pinfunction "GND_99") (pintype "power_in"))
      (node (ref "J701") (pin "1") (pinfunction "GND_1") (pintype "passive"))
      (node (ref "J701") (pin "105") (pinfunction "GND_105") (pintype "passive"))
      (node (ref "J701") (pin "11") (pinfunction "GND_11") (pintype "passive"))
      (node (ref "J701") (pin "118") (pinfunction "GND_118") (pintype "passive"))
      (node (ref "J701") (pin "121") (pinfunction "GND_121") (pintype "passive"))
      (node (ref "J701") (pin "134") (pinfunction "GND_134") (pintype "passive"))
      (node (ref "J701") (pin "137") (pinfunction "GND_137") (pintype "passive"))
      (node (ref "J701") (pin "14") (pinfunction "GND_14") (pintype "passive"))
      (node (ref "J701") (pin "146") (pinfunction "GND_146") (pintype "passive"))
      (node (ref "J701") (pin "149") (pinfunction "GND_149") (pintype "passive"))
      (node (ref "J701") (pin "15") (pinfunction "GND_15") (pintype "passive"))
      (node (ref "J701") (pin "158") (pinfunction "GND_158") (pintype "passive"))
      (node (ref "J701") (pin "161") (pinfunction "GND_161") (pintype "passive"))
      (node (ref "J701") (pin "18") (pinfunction "GND_18") (pintype "passive"))
      (node (ref "J701") (pin "19") (pinfunction "GND_19") (pintype "passive"))
      (node (ref "J701") (pin "2") (pinfunction "GND_2") (pintype "passive"))
      (node (ref "J701") (pin "22") (pinfunction "GND_22") (pintype "passive"))
      (node (ref "J701") (pin "23") (pinfunction "GND_23") (pintype "passive"))
      (node (ref "J701") (pin "26") (pinfunction "GND_26") (pintype "passive"))
      (node (ref "J701") (pin "27") (pinfunction "GND_27") (pintype "passive"))
      (node (ref "J701") (pin "30") (pinfunction "GND_30") (pintype "passive"))
      (node (ref "J701") (pin "31") (pinfunction "GND_31") (pintype "passive"))
      (node (ref "J701") (pin "34") (pinfunction "GND_34") (pintype "passive"))
      (node (ref "J701") (pin "35") (pinfunction "GND_35") (pintype "passive"))
      (node (ref "J701") (pin "38") (pinfunction "GND_38") (pintype "passive"))
      (node (ref "J701") (pin "39") (pinfunction "GND_39") (pintype "passive"))
      (node (ref "J701") (pin "42") (pinfunction "GND_42") (pintype "passive"))
      (node (ref "J701") (pin "43") (pinfunction "GND_43") (pintype "passive"))
      (node (ref "J701") (pin "46") (pinfunction "GND_46") (pintype "passive"))
      (node (ref "J701") (pin "49") (pinfunction "GND_49") (pintype "passive"))
      (node (ref "J701") (pin "58") (pinfunction "GND_58") (pintype "passive"))
      (node (ref "J701") (pin "61") (pinfunction "GND_61") (pintype "passive"))
      (node (ref "J701") (pin "70") (pinfunction "GND_70") (pintype "passive"))
      (node (ref "J701") (pin "73") (pinfunction "GND_73") (pintype "passive"))
      (node (ref "J701") (pin "82") (pinfunction "GND_82") (pintype "passive"))
      (node (ref "J701") (pin "85") (pinfunction "GND_85") (pintype "passive"))
      (node (ref "J701") (pin "98") (pinfunction "GND_98") (pintype "passive"))
    )
    (net (code "191") (name "DVDD25") (class "Default")
      (node (ref "J700") (pin "38") (pinfunction "VIN_IO_38") (pintype "power_in"))
      (node (ref "J700") (pin "41") (pinfunction "VIN_IO_41") (pintype "power_in"))
      (node (ref "J700") (pin "74") (pinfunction "VIN_CFG_74") (pintype "power_in"))
      (node (ref "J700") (pin "77") (pinfunction "VIN_CFG_77") (pintype "power_in"))
      (node (ref "J701") (pin "140") (pinfunction "VIN_IO_140") (pintype "passive"))
      (node (ref "J701") (pin "143") (pinfunction "VIN_IO_143") (pintype "passive"))
      (node (ref "J701") (pin "64") (pinfunction "VIN_IO_64") (pintype "passive"))
      (node (ref "J701") (pin "67") (pinfunction "VIN_IO_67") (pintype "passive"))
      (node (ref "J701") (pin "88") (pinfunction "VIN_IO_88") (pintype "passive"))
      (node (ref "J701") (pin "95") (pinfunction "VIN_IO_95") (pintype "passive"))
    )
    (net (code "192") (name "DVDD33") (class "Default")
      (node (ref "J700") (pin "10") (pinfunction "PWR_EN_10") (pintype "passive"))
    )
    (net (code "193") (name "unconnected-(J700-ETH_CTREF-Pad154)") (class "Default")
      (node (ref "J700") (pin "154") (pinfunction "ETH_CTREF_154") (pintype "passive"))
    )
    (net (code "194") (name "unconnected-(J700-ETH_LED1#-Pad148)") (class "Default")
      (node (ref "J700") (pin "148") (pinfunction "ETH_LED1#_148") (pintype "passive"))
    )
    (net (code "195") (name "unconnected-(J700-ETH_LED2#-Pad160)") (class "Default")
      (node (ref "J700") (pin "160") (pinfunction "ETH_LED2#_160") (pintype "passive"))
    )
    (net (code "196") (name "unconnected-(J700-GND-Pad139)") (class "Default")
      (node (ref "J700") (pin "139") (pinfunction "GND_139") (pintype "power_in"))
    )
    (net (code "197") (name "unconnected-(J700-IO_P-Pad79)") (class "Default")
      (node (ref "J700") (pin "79") (pinfunction "IO_P_79") (pintype "passive"))
    )
    (net (code "198") (name "unconnected-(J700-VIN_BAT-Pad168)") (class "Default")
      (node (ref "J700") (pin "168") (pinfunction "VIN_BAT_168") (pintype "power_in"))
    )
    (net (code "199") (name "unconnected-(J700-VOUT-Pad53)") (class "Default")
      (node (ref "J700") (pin "53") (pinfunction "VOUT_53") (pintype "power_in"))
    )
    (net (code "200") (name "unconnected-(J700-VOUT-Pad62)") (class "Default")
      (node (ref "J700") (pin "62") (pinfunction "VOUT_62") (pintype "power_in"))
    )
    (net (code "201") (name "unconnected-(J700-VOUT-Pad65)") (class "Default")
      (node (ref "J700") (pin "65") (pinfunction "VOUT_65") (pintype "power_in"))
    )
    (net (code "202") (name "unconnected-(J700-VOUT-Pad89)") (class "Default")
      (node (ref "J700") (pin "89") (pinfunction "VOUT_89") (pintype "power_in"))
    )
    (net (code "203") (name "unconnected-(J700-VOUT_3V3-Pad26)") (class "Default")
      (node (ref "J700") (pin "26") (pinfunction "VOUT_3V3_26") (pintype "power_in"))
    )
    (net (code "204") (name "unconnected-(J700-VOUT_3V3-Pad29)") (class "Default")
      (node (ref "J700") (pin "29") (pinfunction "VOUT_3V3_29") (pintype "power_in"))
    )
    (net (code "205") (name "unconnected-(J700-VOUT_3V3-Pad50)") (class "Default")
      (node (ref "J700") (pin "50") (pinfunction "VOUT_3V3_50") (pintype "power_in"))
    )
    (net (code "206") (name "unconnected-(J700-VOUT_3V3-Pad86)") (class "Default")
      (node (ref "J700") (pin "86") (pinfunction "VOUT_3V3_86") (pintype "power_in"))
    )
    (net (code "207") (name "unconnected-(J701-IO_N-Pad9)") (class "Default")
      (node (ref "J701") (pin "9") (pinfunction "IO_N_9") (pintype "passive"))
    )
    (net (code "208") (name "unconnected-(J701-IO_N-Pad47)") (class "Default")
      (node (ref "J701") (pin "47") (pinfunction "IO_N_47") (pintype "passive"))
    )
    (net (code "209") (name "unconnected-(J701-IO_N-Pad50)") (class "Default")
      (node (ref "J701") (pin "50") (pinfunction "IO_N_50") (pintype "passive"))
    )
    (net (code "210") (name "unconnected-(J701-IO_N-Pad53)") (class "Default")
      (node (ref "J701") (pin "53") (pinfunction "IO_N_53") (pintype "passive"))
    )
    (net (code "211") (name "unconnected-(J701-IO_N-Pad56)") (class "Default")
      (node (ref "J701") (pin "56") (pinfunction "IO_N_56") (pintype "passive"))
    )
    (net (code "212") (name "unconnected-(J701-IO_N-Pad62)") (class "Default")
      (node (ref "J701") (pin "62") (pinfunction "IO_N_62") (pintype "passive"))
    )
    (net (code "213") (name "unconnected-(J701-IO_N-Pad65)") (class "Default")
      (node (ref "J701") (pin "65") (pinfunction "IO_N_65") (pintype "passive"))
    )
    (net (code "214") (name "unconnected-(J701-IO_N-Pad68)") (class "Default")
      (node (ref "J701") (pin "68") (pinfunction "IO_N_68") (pintype "passive"))
    )
    (net (code "215") (name "unconnected-(J701-IO_N-Pad71)") (class "Default")
      (node (ref "J701") (pin "71") (pinfunction "IO_N_71") (pintype "passive"))
    )
    (net (code "216") (name "unconnected-(J701-IO_P-Pad7)") (class "Default")
      (node (ref "J701") (pin "7") (pinfunction "IO_P_7") (pintype "passive"))
    )
    (net (code "217") (name "unconnected-(J701-IO_P-Pad45)") (class "Default")
      (node (ref "J701") (pin "45") (pinfunction "IO_P_45") (pintype "passive"))
    )
    (net (code "218") (name "unconnected-(J701-IO_P-Pad48)") (class "Default")
      (node (ref "J701") (pin "48") (pinfunction "IO_P_48") (pintype "passive"))
    )
    (net (code "219") (name "unconnected-(J701-IO_P-Pad51)") (class "Default")
      (node (ref "J701") (pin "51") (pinfunction "IO_P_51") (pintype "passive"))
    )
    (net (code "220") (name "unconnected-(J701-IO_P-Pad54)") (class "Default")
      (node (ref "J701") (pin "54") (pinfunction "IO_P_54") (pintype "passive"))
    )
    (net (code "221") (name "unconnected-(J701-IO_P-Pad60)") (class "Default")
      (node (ref "J701") (pin "60") (pinfunction "IO_P_60") (pintype "passive"))
    )
    (net (code "222") (name "unconnected-(J701-IO_P-Pad63)") (class "Default")
      (node (ref "J701") (pin "63") (pinfunction "IO_P_63") (pintype "passive"))
    )
    (net (code "223") (name "unconnected-(J701-IO_P-Pad66)") (class "Default")
      (node (ref "J701") (pin "66") (pinfunction "IO_P_66") (pintype "passive"))
    )
    (net (code "224") (name "unconnected-(J701-IO_P-Pad69)") (class "Default")
      (node (ref "J701") (pin "69") (pinfunction "IO_P_69") (pintype "passive"))
    )
    (net (code "225") (name "unconnected-(J701-MGT_CLK_N-Pad6)") (class "Default")
      (node (ref "J701") (pin "6") (pinfunction "MGT_CLK_N_6") (pintype "passive"))
    )
    (net (code "226") (name "unconnected-(J701-MGT_CLK_N-Pad12)") (class "Default")
      (node (ref "J701") (pin "12") (pinfunction "MGT_CLK_N_12") (pintype "passive"))
    )
    (net (code "227") (name "unconnected-(J701-MGT_CLK_P-Pad4)") (class "Default")
      (node (ref "J701") (pin "4") (pinfunction "MGT_CLK_P_4") (pintype "passive"))
    )
    (net (code "228") (name "unconnected-(J701-MGT_CLK_P-Pad10)") (class "Default")
      (node (ref "J701") (pin "10") (pinfunction "MGT_CLK_P_10") (pintype "passive"))
    )
    (net (code "229") (name "unconnected-(J701-MGT_RX_N-Pad20)") (class "Default")
      (node (ref "J701") (pin "20") (pinfunction "MGT_RX_N_20") (pintype "passive"))
    )
    (net (code "230") (name "unconnected-(J701-MGT_RX_N-Pad28)") (class "Default")
      (node (ref "J701") (pin "28") (pinfunction "MGT_RX_N_28") (pintype "passive"))
    )
    (net (code "231") (name "unconnected-(J701-MGT_RX_N-Pad36)") (class "Default")
      (node (ref "J701") (pin "36") (pinfunction "MGT_RX_N_36") (pintype "passive"))
    )
    (net (code "232") (name "unconnected-(J701-MGT_RX_N-Pad44)") (class "Default")
      (node (ref "J701") (pin "44") (pinfunction "MGT_RX_N_44") (pintype "passive"))
    )
    (net (code "233") (name "unconnected-(J701-MGT_RX_P-Pad16)") (class "Default")
      (node (ref "J701") (pin "16") (pinfunction "MGT_RX_P_16") (pintype "passive"))
    )
    (net (code "234") (name "unconnected-(J701-MGT_RX_P-Pad24)") (class "Default")
      (node (ref "J701") (pin "24") (pinfunction "MGT_RX_P_24") (pintype "passive"))
    )
    (net (code "235") (name "unconnected-(J701-MGT_RX_P-Pad32)") (class "Default")
      (node (ref "J701") (pin "32") (pinfunction "MGT_RX_P_32") (pintype "passive"))
    )
    (net (code "236") (name "unconnected-(J701-MGT_RX_P-Pad40)") (class "Default")
      (node (ref "J701") (pin "40") (pinfunction "MGT_RX_P_40") (pintype "passive"))
    )
    (net (code "237") (name "unconnected-(J701-MGT_TX_N-Pad17)") (class "Default")
      (node (ref "J701") (pin "17") (pinfunction "MGT_TX_N_17") (pintype "passive"))
    )
    (net (code "238") (name "unconnected-(J701-MGT_TX_N-Pad25)") (class "Default")
      (node (ref "J701") (pin "25") (pinfunction "MGT_TX_N_25") (pintype "passive"))
    )
    (net (code "239") (name "unconnected-(J701-MGT_TX_N-Pad33)") (class "Default")
      (node (ref "J701") (pin "33") (pinfunction "MGT_TX_N_33") (pintype "passive"))
    )
    (net (code "240") (name "unconnected-(J701-MGT_TX_N-Pad41)") (class "Default")
      (node (ref "J701") (pin "41") (pinfunction "MGT_TX_N_41") (pintype "passive"))
    )
    (net (code "241") (name "unconnected-(J701-MGT_TX_P-Pad13)") (class "Default")
      (node (ref "J701") (pin "13") (pinfunction "MGT_TX_P_13") (pintype "passive"))
    )
    (net (code "242") (name "unconnected-(J701-MGT_TX_P-Pad21)") (class "Default")
      (node (ref "J701") (pin "21") (pinfunction "MGT_TX_P_21") (pintype "passive"))
    )
    (net (code "243") (name "unconnected-(J701-MGT_TX_P-Pad29)") (class "Default")
      (node (ref "J701") (pin "29") (pinfunction "MGT_TX_P_29") (pintype "passive"))
    )
    (net (code "244") (name "unconnected-(J701-MGT_TX_P-Pad37)") (class "Default")
      (node (ref "J701") (pin "37") (pinfunction "MGT_TX_P_37") (pintype "passive"))
    )
    (net (code "245") (name "unconnected-(J701-SCLK_N-Pad5)") (class "Default")
      (node (ref "J701") (pin "5") (pinfunction "SCLK_N_5") (pintype "passive"))
    )
    (net (code "246") (name "unconnected-(J701-SCLK_P-Pad3)") (class "Default")
      (node (ref "J701") (pin "3") (pinfunction "SCLK_P_3") (pintype "passive"))
    )
    (net (code "247") (name "unconnected-(J701-VOUT-Pad52)") (class "Default")
      (node (ref "J701") (pin "52") (pinfunction "VOUT_52") (pintype "passive"))
    )
    (net (code "248") (name "unconnected-(J701-VOUT-Pad76)") (class "Default")
      (node (ref "J701") (pin "76") (pinfunction "VOUT_76") (pintype "passive"))
    )
    (net (code "249") (name "unconnected-(J701-VOUT-Pad108)") (class "Default")
      (node (ref "J701") (pin "108") (pinfunction "VOUT_108") (pintype "passive"))
    )
    (net (code "250") (name "unconnected-(J701-VOUT-Pad128)") (class "Default")
      (node (ref "J701") (pin "128") (pinfunction "VOUT_128") (pintype "passive"))
    )
    (net (code "251") (name "unconnected-(J701-VOUT_3V3-Pad55)") (class "Default")
      (node (ref "J701") (pin "55") (pinfunction "VOUT_3V3_55") (pintype "passive"))
    )
    (net (code "252") (name "unconnected-(J701-VOUT_3V3-Pad79)") (class "Default")
      (node (ref "J701") (pin "79") (pinfunction "VOUT_3V3_79") (pintype "passive"))
    )
    (net (code "253") (name "unconnected-(J701-VOUT_3V3-Pad115)") (class "Default")
      (node (ref "J701") (pin "115") (pinfunction "VOUT_3V3_115") (pintype "passive"))
    )
    (net (code "254") (name "unconnected-(J701-VOUT_3V3-Pad127)") (class "Default")
      (node (ref "J701") (pin "127") (pinfunction "VOUT_3V3_127") (pintype "passive"))
    )
    (net (code "255") (name "unconnected-(J701-VOUT_3V3-Pad152)") (class "Default")
      (node (ref "J701") (pin "152") (pinfunction "VOUT_3V3_152") (pintype "passive"))
    )
    (net (code "256") (name "unconnected-(J701-VOUT_3V3-Pad155)") (class "Default")
      (node (ref "J701") (pin "155") (pinfunction "VOUT_3V3_155") (pintype "passive"))
    )
    (net (code "257") (name "unconnected-(J800-GND-Pad1)") (class "Default")
      (node (ref "J800") (pin "1") (pinfunction "GND_1") (pintype "passive"))
    )
    (net (code "258") (name "unconnected-(J800-GND-Pad2)") (class "Default")
      (node (ref "J800") (pin "2") (pinfunction "GND_2") (pintype "passive"))
    )
    (net (code "259") (name "unconnected-(J800-GND-Pad11)") (class "Default")
      (node (ref "J800") (pin "11") (pinfunction "GND_11") (pintype "passive"))
    )
    (net (code "260") (name "unconnected-(J800-GND-Pad14)") (class "Default")
      (node (ref "J800") (pin "14") (pinfunction "GND_14") (pintype "passive"))
    )
    (net (code "261") (name "unconnected-(J800-GND-Pad15)") (class "Default")
      (node (ref "J800") (pin "15") (pinfunction "GND_15") (pintype "passive"))
    )
    (net (code "262") (name "unconnected-(J800-GND-Pad18)") (class "Default")
      (node (ref "J800") (pin "18") (pinfunction "GND_18") (pintype "passive"))
    )
    (net (code "263") (name "unconnected-(J800-GND-Pad19)") (class "Default")
      (node (ref "J800") (pin "19") (pinfunction "GND_19") (pintype "passive"))
    )
    (net (code "264") (name "unconnected-(J800-GND-Pad22)") (class "Default")
      (node (ref "J800") (pin "22") (pinfunction "GND_22") (pintype "passive"))
    )
    (net (code "265") (name "unconnected-(J800-GND-Pad23)") (class "Default")
      (node (ref "J800") (pin "23") (pinfunction "GND_23") (pintype "passive"))
    )
    (net (code "266") (name "unconnected-(J800-GND-Pad26)") (class "Default")
      (node (ref "J800") (pin "26") (pinfunction "GND_26") (pintype "passive"))
    )
    (net (code "267") (name "unconnected-(J800-GND-Pad27)") (class "Default")
      (node (ref "J800") (pin "27") (pinfunction "GND_27") (pintype "passive"))
    )
    (net (code "268") (name "unconnected-(J800-GND-Pad30)") (class "Default")
      (node (ref "J800") (pin "30") (pinfunction "GND_30") (pintype "passive"))
    )
    (net (code "269") (name "unconnected-(J800-GND-Pad31)") (class "Default")
      (node (ref "J800") (pin "31") (pinfunction "GND_31") (pintype "passive"))
    )
    (net (code "270") (name "unconnected-(J800-GND-Pad34)") (class "Default")
      (node (ref "J800") (pin "34") (pinfunction "GND_34") (pintype "passive"))
    )
    (net (code "271") (name "unconnected-(J800-GND-Pad35)") (class "Default")
      (node (ref "J800") (pin "35") (pinfunction "GND_35") (pintype "passive"))
    )
    (net (code "272") (name "unconnected-(J800-GND-Pad38)") (class "Default")
      (node (ref "J800") (pin "38") (pinfunction "GND_38") (pintype "passive"))
    )
    (net (code "273") (name "unconnected-(J800-GND-Pad39)") (class "Default")
      (node (ref "J800") (pin "39") (pinfunction "GND_39") (pintype "passive"))
    )
    (net (code "274") (name "unconnected-(J800-GND-Pad42)") (class "Default")
      (node (ref "J800") (pin "42") (pinfunction "GND_42") (pintype "passive"))
    )
    (net (code "275") (name "unconnected-(J800-GND-Pad43)") (class "Default")
      (node (ref "J800") (pin "43") (pinfunction "GND_43") (pintype "passive"))
    )
    (net (code "276") (name "unconnected-(J800-GND-Pad46)") (class "Default")
      (node (ref "J800") (pin "46") (pinfunction "GND_46") (pintype "passive"))
    )
    (net (code "277") (name "unconnected-(J800-GND-Pad49)") (class "Default")
      (node (ref "J800") (pin "49") (pinfunction "GND_49") (pintype "passive"))
    )
    (net (code "278") (name "unconnected-(J800-GND-Pad52)") (class "Default")
      (node (ref "J800") (pin "52") (pinfunction "GND_52") (pintype "passive"))
    )
    (net (code "279") (name "unconnected-(J800-GND-Pad55)") (class "Default")
      (node (ref "J800") (pin "55") (pinfunction "GND_55") (pintype "passive"))
    )
    (net (code "280") (name "unconnected-(J800-GND-Pad58)") (class "Default")
      (node (ref "J800") (pin "58") (pinfunction "GND_58") (pintype "passive"))
    )
    (net (code "281") (name "unconnected-(J800-GND-Pad61)") (class "Default")
      (node (ref "J800") (pin "61") (pinfunction "GND_61") (pintype "passive"))
    )
    (net (code "282") (name "unconnected-(J800-GND-Pad64)") (class "Default")
      (node (ref "J800") (pin "64") (pinfunction "GND_64") (pintype "passive"))
    )
    (net (code "283") (name "unconnected-(J800-GND-Pad67)") (class "Default")
      (node (ref "J800") (pin "67") (pinfunction "GND_67") (pintype "passive"))
    )
    (net (code "284") (name "unconnected-(J800-GND-Pad70)") (class "Default")
      (node (ref "J800") (pin "70") (pinfunction "GND_70") (pintype "passive"))
    )
    (net (code "285") (name "unconnected-(J800-GND-Pad73)") (class "Default")
      (node (ref "J800") (pin "73") (pinfunction "GND_73") (pintype "passive"))
    )
    (net (code "286") (name "unconnected-(J800-GND-Pad86)") (class "Default")
      (node (ref "J800") (pin "86") (pinfunction "GND_86") (pintype "passive"))
    )
    (net (code "287") (name "unconnected-(J800-GND-Pad93)") (class "Default")
      (node (ref "J800") (pin "93") (pinfunction "GND_93") (pintype "passive"))
    )
    (net (code "288") (name "unconnected-(J800-GND-Pad106)") (class "Default")
      (node (ref "J800") (pin "106") (pinfunction "GND_106") (pintype "passive"))
    )
    (net (code "289") (name "unconnected-(J800-GND-Pad113)") (class "Default")
      (node (ref "J800") (pin "113") (pinfunction "GND_113") (pintype "passive"))
    )
    (net (code "290") (name "unconnected-(J800-GND-Pad126)") (class "Default")
      (node (ref "J800") (pin "126") (pinfunction "GND_126") (pintype "passive"))
    )
    (net (code "291") (name "unconnected-(J800-GND-Pad133)") (class "Default")
      (node (ref "J800") (pin "133") (pinfunction "GND_133") (pintype "passive"))
    )
    (net (code "292") (name "unconnected-(J800-GND-Pad146)") (class "Default")
      (node (ref "J800") (pin "146") (pinfunction "GND_146") (pintype "passive"))
    )
    (net (code "293") (name "unconnected-(J800-GND-Pad149)") (class "Default")
      (node (ref "J800") (pin "149") (pinfunction "GND_149") (pintype "passive"))
    )
    (net (code "294") (name "unconnected-(J800-GND-Pad152)") (class "Default")
      (node (ref "J800") (pin "152") (pinfunction "GND_152") (pintype "passive"))
    )
    (net (code "295") (name "unconnected-(J800-GND-Pad155)") (class "Default")
      (node (ref "J800") (pin "155") (pinfunction "GND_155") (pintype "passive"))
    )
    (net (code "296") (name "unconnected-(J800-GND-Pad168)") (class "Default")
      (node (ref "J800") (pin "168") (pinfunction "GND_168") (pintype "passive"))
    )
    (net (code "297") (name "unconnected-(J800-IO_N-Pad5)") (class "Default")
      (node (ref "J800") (pin "5") (pinfunction "IO_N_5") (pintype "passive"))
    )
    (net (code "298") (name "unconnected-(J800-IO_N-Pad9)") (class "Default")
      (node (ref "J800") (pin "9") (pinfunction "IO_N_9") (pintype "passive"))
    )
    (net (code "299") (name "unconnected-(J800-IO_N-Pad47)") (class "Default")
      (node (ref "J800") (pin "47") (pinfunction "IO_N_47") (pintype "passive"))
    )
    (net (code "300") (name "unconnected-(J800-IO_N-Pad50)") (class "Default")
      (node (ref "J800") (pin "50") (pinfunction "IO_N_50") (pintype "passive"))
    )
    (net (code "301") (name "unconnected-(J800-IO_N-Pad53)") (class "Default")
      (node (ref "J800") (pin "53") (pinfunction "IO_N_53") (pintype "passive"))
    )
    (net (code "302") (name "unconnected-(J800-IO_N-Pad56)") (class "Default")
      (node (ref "J800") (pin "56") (pinfunction "IO_N_56") (pintype "passive"))
    )
    (net (code "303") (name "unconnected-(J800-IO_N-Pad59)") (class "Default")
      (node (ref "J800") (pin "59") (pinfunction "IO_N_59") (pintype "passive"))
    )
    (net (code "304") (name "unconnected-(J800-IO_N-Pad62)") (class "Default")
      (node (ref "J800") (pin "62") (pinfunction "IO_N_62") (pintype "passive"))
    )
    (net (code "305") (name "unconnected-(J800-IO_N-Pad65)") (class "Default")
      (node (ref "J800") (pin "65") (pinfunction "IO_N_65") (pintype "passive"))
    )
    (net (code "306") (name "unconnected-(J800-IO_N-Pad68)") (class "Default")
      (node (ref "J800") (pin "68") (pinfunction "IO_N_68") (pintype "passive"))
    )
    (net (code "307") (name "unconnected-(J800-IO_N-Pad77)") (class "Default")
      (node (ref "J800") (pin "77") (pinfunction "IO_N_77") (pintype "passive"))
    )
    (net (code "308") (name "unconnected-(J800-IO_N-Pad80)") (class "Default")
      (node (ref "J800") (pin "80") (pinfunction "IO_N_80") (pintype "passive"))
    )
    (net (code "309") (name "unconnected-(J800-IO_N-Pad81)") (class "Default")
      (node (ref "J800") (pin "81") (pinfunction "IO_N_81") (pintype "passive"))
    )
    (net (code "310") (name "unconnected-(J800-IO_N-Pad84)") (class "Default")
      (node (ref "J800") (pin "84") (pinfunction "IO_N_84") (pintype "passive"))
    )
    (net (code "311") (name "unconnected-(J800-IO_N-Pad87)") (class "Default")
      (node (ref "J800") (pin "87") (pinfunction "IO_N_87") (pintype "passive"))
    )
    (net (code "312") (name "unconnected-(J800-IO_N-Pad94)") (class "Default")
      (node (ref "J800") (pin "94") (pinfunction "IO_N_94") (pintype "passive"))
    )
    (net (code "313") (name "unconnected-(J800-IO_N-Pad97)") (class "Default")
      (node (ref "J800") (pin "97") (pinfunction "IO_N_97") (pintype "passive"))
    )
    (net (code "314") (name "unconnected-(J800-IO_N-Pad100)") (class "Default")
      (node (ref "J800") (pin "100") (pinfunction "IO_N_100") (pintype "passive"))
    )
    (net (code "315") (name "unconnected-(J800-IO_N-Pad101)") (class "Default")
      (node (ref "J800") (pin "101") (pinfunction "IO_N_101") (pintype "passive"))
    )
    (net (code "316") (name "unconnected-(J800-IO_N-Pad104)") (class "Default")
      (node (ref "J800") (pin "104") (pinfunction "IO_N_104") (pintype "passive"))
    )
    (net (code "317") (name "unconnected-(J800-IO_N-Pad107)") (class "Default")
      (node (ref "J800") (pin "107") (pinfunction "IO_N_107") (pintype "passive"))
    )
    (net (code "318") (name "unconnected-(J800-IO_N-Pad110)") (class "Default")
      (node (ref "J800") (pin "110") (pinfunction "IO_N_110") (pintype "passive"))
    )
    (net (code "319") (name "unconnected-(J800-IO_N-Pad111)") (class "Default")
      (node (ref "J800") (pin "111") (pinfunction "IO_N_111") (pintype "passive"))
    )
    (net (code "320") (name "unconnected-(J800-IO_N-Pad114)") (class "Default")
      (node (ref "J800") (pin "114") (pinfunction "IO_N_114") (pintype "passive"))
    )
    (net (code "321") (name "unconnected-(J800-IO_N-Pad120)") (class "Default")
      (node (ref "J800") (pin "120") (pinfunction "IO_N_120") (pintype "passive"))
    )
    (net (code "322") (name "unconnected-(J800-IO_N-Pad121)") (class "Default")
      (node (ref "J800") (pin "121") (pinfunction "IO_N_121") (pintype "passive"))
    )
    (net (code "323") (name "unconnected-(J800-IO_N-Pad127)") (class "Default")
      (node (ref "J800") (pin "127") (pinfunction "IO_N_127") (pintype "passive"))
    )
    (net (code "324") (name "unconnected-(J800-IO_N-Pad130)") (class "Default")
      (node (ref "J800") (pin "130") (pinfunction "IO_N_130") (pintype "passive"))
    )
    (net (code "325") (name "unconnected-(J800-IO_N-Pad131)") (class "Default")
      (node (ref "J800") (pin "131") (pinfunction "IO_N_131") (pintype "passive"))
    )
    (net (code "326") (name "unconnected-(J800-IO_N-Pad134)") (class "Default")
      (node (ref "J800") (pin "134") (pinfunction "IO_N_134") (pintype "passive"))
    )
    (net (code "327") (name "unconnected-(J800-IO_N-Pad137)") (class "Default")
      (node (ref "J800") (pin "137") (pinfunction "IO_N_137") (pintype "passive"))
    )
    (net (code "328") (name "unconnected-(J800-IO_N-Pad140)") (class "Default")
      (node (ref "J800") (pin "140") (pinfunction "IO_N_140") (pintype "passive"))
    )
    (net (code "329") (name "unconnected-(J800-IO_N-Pad141)") (class "Default")
      (node (ref "J800") (pin "141") (pinfunction "IO_N_141") (pintype "passive"))
    )
    (net (code "330") (name "unconnected-(J800-IO_N-Pad144)") (class "Default")
      (node (ref "J800") (pin "144") (pinfunction "IO_N_144") (pintype "passive"))
    )
    (net (code "331") (name "unconnected-(J800-IO_N-Pad147)") (class "Default")
      (node (ref "J800") (pin "147") (pinfunction "IO_N_147") (pintype "passive"))
    )
    (net (code "332") (name "unconnected-(J800-IO_N-Pad156)") (class "Default")
      (node (ref "J800") (pin "156") (pinfunction "IO_N_156") (pintype "passive"))
    )
    (net (code "333") (name "unconnected-(J800-IO_N-Pad159)") (class "Default")
      (node (ref "J800") (pin "159") (pinfunction "IO_N_159") (pintype "passive"))
    )
    (net (code "334") (name "unconnected-(J800-IO_N-Pad162)") (class "Default")
      (node (ref "J800") (pin "162") (pinfunction "IO_N_162") (pintype "passive"))
    )
    (net (code "335") (name "unconnected-(J800-IO_N-Pad163)") (class "Default")
      (node (ref "J800") (pin "163") (pinfunction "IO_N_163") (pintype "passive"))
    )
    (net (code "336") (name "unconnected-(J800-IO_N-Pad166)") (class "Default")
      (node (ref "J800") (pin "166") (pinfunction "IO_N_166") (pintype "passive"))
    )
    (net (code "337") (name "unconnected-(J800-IO_P-Pad3)") (class "Default")
      (node (ref "J800") (pin "3") (pinfunction "IO_P_3") (pintype "passive"))
    )
    (net (code "338") (name "unconnected-(J800-IO_P-Pad7)") (class "Default")
      (node (ref "J800") (pin "7") (pinfunction "IO_P_7") (pintype "passive"))
    )
    (net (code "339") (name "unconnected-(J800-IO_P-Pad45)") (class "Default")
      (node (ref "J800") (pin "45") (pinfunction "IO_P_45") (pintype "passive"))
    )
    (net (code "340") (name "unconnected-(J800-IO_P-Pad48)") (class "Default")
      (node (ref "J800") (pin "48") (pinfunction "IO_P_48") (pintype "passive"))
    )
    (net (code "341") (name "unconnected-(J800-IO_P-Pad51)") (class "Default")
      (node (ref "J800") (pin "51") (pinfunction "IO_P_51") (pintype "passive"))
    )
    (net (code "342") (name "unconnected-(J800-IO_P-Pad54)") (class "Default")
      (node (ref "J800") (pin "54") (pinfunction "IO_P_54") (pintype "passive"))
    )
    (net (code "343") (name "unconnected-(J800-IO_P-Pad57)") (class "Default")
      (node (ref "J800") (pin "57") (pinfunction "IO_P_57") (pintype "passive"))
    )
    (net (code "344") (name "unconnected-(J800-IO_P-Pad60)") (class "Default")
      (node (ref "J800") (pin "60") (pinfunction "IO_P_60") (pintype "passive"))
    )
    (net (code "345") (name "unconnected-(J800-IO_P-Pad63)") (class "Default")
      (node (ref "J800") (pin "63") (pinfunction "IO_P_63") (pintype "passive"))
    )
    (net (code "346") (name "unconnected-(J800-IO_P-Pad66)") (class "Default")
      (node (ref "J800") (pin "66") (pinfunction "IO_P_66") (pintype "passive"))
    )
    (net (code "347") (name "unconnected-(J800-IO_P-Pad75)") (class "Default")
      (node (ref "J800") (pin "75") (pinfunction "IO_P_75") (pintype "passive"))
    )
    (net (code "348") (name "unconnected-(J800-IO_P-Pad78)") (class "Default")
      (node (ref "J800") (pin "78") (pinfunction "IO_P_78") (pintype "passive"))
    )
    (net (code "349") (name "unconnected-(J800-IO_P-Pad79)") (class "Default")
      (node (ref "J800") (pin "79") (pinfunction "IO_P_79") (pintype "passive"))
    )
    (net (code "350") (name "unconnected-(J800-IO_P-Pad82)") (class "Default")
      (node (ref "J800") (pin "82") (pinfunction "IO_P_82") (pintype "passive"))
    )
    (net (code "351") (name "unconnected-(J800-IO_P-Pad85)") (class "Default")
      (node (ref "J800") (pin "85") (pinfunction "IO_P_85") (pintype "passive"))
    )
    (net (code "352") (name "unconnected-(J800-IO_P-Pad92)") (class "Default")
      (node (ref "J800") (pin "92") (pinfunction "IO_P_92") (pintype "passive"))
    )
    (net (code "353") (name "unconnected-(J800-IO_P-Pad95)") (class "Default")
      (node (ref "J800") (pin "95") (pinfunction "IO_P_95") (pintype "passive"))
    )
    (net (code "354") (name "unconnected-(J800-IO_P-Pad98)") (class "Default")
      (node (ref "J800") (pin "98") (pinfunction "IO_P_98") (pintype "passive"))
    )
    (net (code "355") (name "unconnected-(J800-IO_P-Pad99)") (class "Default")
      (node (ref "J800") (pin "99") (pinfunction "IO_P_99") (pintype "passive"))
    )
    (net (code "356") (name "unconnected-(J800-IO_P-Pad102)") (class "Default")
      (node (ref "J800") (pin "102") (pinfunction "IO_P_102") (pintype "passive"))
    )
    (net (code "357") (name "unconnected-(J800-IO_P-Pad105)") (class "Default")
      (node (ref "J800") (pin "105") (pinfunction "IO_P_105") (pintype "passive"))
    )
    (net (code "358") (name "unconnected-(J800-IO_P-Pad108)") (class "Default")
      (node (ref "J800") (pin "108") (pinfunction "IO_P_108") (pintype "passive"))
    )
    (net (code "359") (name "unconnected-(J800-IO_P-Pad109)") (class "Default")
      (node (ref "J800") (pin "109") (pinfunction "IO_P_109") (pintype "passive"))
    )
    (net (code "360") (name "unconnected-(J800-IO_P-Pad112)") (class "Default")
      (node (ref "J800") (pin "112") (pinfunction "IO_P_112") (pintype "passive"))
    )
    (net (code "361") (name "unconnected-(J800-IO_P-Pad118)") (class "Default")
      (node (ref "J800") (pin "118") (pinfunction "IO_P_118") (pintype "passive"))
    )
    (net (code "362") (name "unconnected-(J800-IO_P-Pad119)") (class "Default")
      (node (ref "J800") (pin "119") (pinfunction "IO_P_119") (pintype "passive"))
    )
    (net (code "363") (name "unconnected-(J800-IO_P-Pad125)") (class "Default")
      (node (ref "J800") (pin "125") (pinfunction "IO_P_125") (pintype "passive"))
    )
    (net (code "364") (name "unconnected-(J800-IO_P-Pad128)") (class "Default")
      (node (ref "J800") (pin "128") (pinfunction "IO_P_128") (pintype "passive"))
    )
    (net (code "365") (name "unconnected-(J800-IO_P-Pad129)") (class "Default")
      (node (ref "J800") (pin "129") (pinfunction "IO_P_129") (pintype "passive"))
    )
    (net (code "366") (name "unconnected-(J800-IO_P-Pad132)") (class "Default")
      (node (ref "J800") (pin "132") (pinfunction "IO_P_132") (pintype "passive"))
    )
    (net (code "367") (name "unconnected-(J800-IO_P-Pad135)") (class "Default")
      (node (ref "J800") (pin "135") (pinfunction "IO_P_135") (pintype "passive"))
    )
    (net (code "368") (name "unconnected-(J800-IO_P-Pad138)") (class "Default")
      (node (ref "J800") (pin "138") (pinfunction "IO_P_138") (pintype "passive"))
    )
    (net (code "369") (name "unconnected-(J800-IO_P-Pad139)") (class "Default")
      (node (ref "J800") (pin "139") (pinfunction "IO_P_139") (pintype "passive"))
    )
    (net (code "370") (name "unconnected-(J800-IO_P-Pad142)") (class "Default")
      (node (ref "J800") (pin "142") (pinfunction "IO_P_142") (pintype "passive"))
    )
    (net (code "371") (name "unconnected-(J800-IO_P-Pad145)") (class "Default")
      (node (ref "J800") (pin "145") (pinfunction "IO_P_145") (pintype "passive"))
    )
    (net (code "372") (name "unconnected-(J800-IO_P-Pad154)") (class "Default")
      (node (ref "J800") (pin "154") (pinfunction "IO_P_154") (pintype "passive"))
    )
    (net (code "373") (name "unconnected-(J800-IO_P-Pad157)") (class "Default")
      (node (ref "J800") (pin "157") (pinfunction "IO_P_157") (pintype "passive"))
    )
    (net (code "374") (name "unconnected-(J800-IO_P-Pad160)") (class "Default")
      (node (ref "J800") (pin "160") (pinfunction "IO_P_160") (pintype "passive"))
    )
    (net (code "375") (name "unconnected-(J800-IO_P-Pad161)") (class "Default")
      (node (ref "J800") (pin "161") (pinfunction "IO_P_161") (pintype "passive"))
    )
    (net (code "376") (name "unconnected-(J800-IO_P-Pad164)") (class "Default")
      (node (ref "J800") (pin "164") (pinfunction "IO_P_164") (pintype "passive"))
    )
    (net (code "377") (name "unconnected-(J800-MGT_RX_N-Pad20)") (class "Default")
      (node (ref "J800") (pin "20") (pinfunction "MGT_RX_N_20") (pintype "passive"))
    )
    (net (code "378") (name "unconnected-(J800-MGT_RX_N-Pad28)") (class "Default")
      (node (ref "J800") (pin "28") (pinfunction "MGT_RX_N_28") (pintype "passive"))
    )
    (net (code "379") (name "unconnected-(J800-MGT_RX_N-Pad36)") (class "Default")
      (node (ref "J800") (pin "36") (pinfunction "MGT_RX_N_36") (pintype "passive"))
    )
    (net (code "380") (name "unconnected-(J800-MGT_RX_N-Pad44)") (class "Default")
      (node (ref "J800") (pin "44") (pinfunction "MGT_RX_N_44") (pintype "passive"))
    )
    (net (code "381") (name "unconnected-(J800-MGT_RX_P-Pad16)") (class "Default")
      (node (ref "J800") (pin "16") (pinfunction "MGT_RX_P_16") (pintype "passive"))
    )
    (net (code "382") (name "unconnected-(J800-MGT_RX_P-Pad24)") (class "Default")
      (node (ref "J800") (pin "24") (pinfunction "MGT_RX_P_24") (pintype "passive"))
    )
    (net (code "383") (name "unconnected-(J800-MGT_RX_P-Pad32)") (class "Default")
      (node (ref "J800") (pin "32") (pinfunction "MGT_RX_P_32") (pintype "passive"))
    )
    (net (code "384") (name "unconnected-(J800-MGT_RX_P-Pad40)") (class "Default")
      (node (ref "J800") (pin "40") (pinfunction "MGT_RX_P_40") (pintype "passive"))
    )
    (net (code "385") (name "unconnected-(J800-MGT_TX_N-Pad17)") (class "Default")
      (node (ref "J800") (pin "17") (pinfunction "MGT_TX_N_17") (pintype "passive"))
    )
    (net (code "386") (name "unconnected-(J800-MGT_TX_N-Pad25)") (class "Default")
      (node (ref "J800") (pin "25") (pinfunction "MGT_TX_N_25") (pintype "passive"))
    )
    (net (code "387") (name "unconnected-(J800-MGT_TX_N-Pad33)") (class "Default")
      (node (ref "J800") (pin "33") (pinfunction "MGT_TX_N_33") (pintype "passive"))
    )
    (net (code "388") (name "unconnected-(J800-MGT_TX_N-Pad41)") (class "Default")
      (node (ref "J800") (pin "41") (pinfunction "MGT_TX_N_41") (pintype "passive"))
    )
    (net (code "389") (name "unconnected-(J800-MGT_TX_P-Pad13)") (class "Default")
      (node (ref "J800") (pin "13") (pinfunction "MGT_TX_P_13") (pintype "passive"))
    )
    (net (code "390") (name "unconnected-(J800-MGT_TX_P-Pad21)") (class "Default")
      (node (ref "J800") (pin "21") (pinfunction "MGT_TX_P_21") (pintype "passive"))
    )
    (net (code "391") (name "unconnected-(J800-MGT_TX_P-Pad29)") (class "Default")
      (node (ref "J800") (pin "29") (pinfunction "MGT_TX_P_29") (pintype "passive"))
    )
    (net (code "392") (name "unconnected-(J800-MGT_TX_P-Pad37)") (class "Default")
      (node (ref "J800") (pin "37") (pinfunction "MGT_TX_P_37") (pintype "passive"))
    )
    (net (code "393") (name "unconnected-(J800-PCLK_N-Pad90)") (class "Default")
      (node (ref "J800") (pin "90") (pinfunction "PCLK_N_90") (pintype "passive"))
    )
    (net (code "394") (name "unconnected-(J800-PCLK_N-Pad150)") (class "Default")
      (node (ref "J800") (pin "150") (pinfunction "PCLK_N_150") (pintype "passive"))
    )
    (net (code "395") (name "unconnected-(J800-PCLK_P-Pad88)") (class "Default")
      (node (ref "J800") (pin "88") (pinfunction "PCLK_P_88") (pintype "passive"))
    )
    (net (code "396") (name "unconnected-(J800-PCLK_P-Pad148)") (class "Default")
      (node (ref "J800") (pin "148") (pinfunction "PCLK_P_148") (pintype "passive"))
    )
    (net (code "397") (name "unconnected-(J800-REFCLK_N-Pad6)") (class "Default")
      (node (ref "J800") (pin "6") (pinfunction "REFCLK_N_6") (pintype "passive"))
    )
    (net (code "398") (name "unconnected-(J800-REFCLK_N-Pad12)") (class "Default")
      (node (ref "J800") (pin "12") (pinfunction "REFCLK_N_12") (pintype "passive"))
    )
    (net (code "399") (name "unconnected-(J800-REFCLK_P-Pad4)") (class "Default")
      (node (ref "J800") (pin "4") (pinfunction "REFCLK_P_4") (pintype "passive"))
    )
    (net (code "400") (name "unconnected-(J800-REFCLK_P-Pad10)") (class "Default")
      (node (ref "J800") (pin "10") (pinfunction "REFCLK_P_10") (pintype "passive"))
    )
    (net (code "401") (name "unconnected-(J800-RSVD-Pad167)") (class "Default")
      (node (ref "J800") (pin "167") (pinfunction "RSVD_167") (pintype "passive"))
    )
    (net (code "402") (name "unconnected-(J800-SCLK_N-Pad71)") (class "Default")
      (node (ref "J800") (pin "71") (pinfunction "SCLK_N_71") (pintype "passive"))
    )
    (net (code "403") (name "unconnected-(J800-SCLK_N-Pad74)") (class "Default")
      (node (ref "J800") (pin "74") (pinfunction "SCLK_N_74") (pintype "passive"))
    )
    (net (code "404") (name "unconnected-(J800-SCLK_N-Pad91)") (class "Default")
      (node (ref "J800") (pin "91") (pinfunction "SCLK_N_91") (pintype "passive"))
    )
    (net (code "405") (name "unconnected-(J800-SCLK_N-Pad117)") (class "Default")
      (node (ref "J800") (pin "117") (pinfunction "SCLK_N_117") (pintype "passive"))
    )
    (net (code "406") (name "unconnected-(J800-SCLK_N-Pad124)") (class "Default")
      (node (ref "J800") (pin "124") (pinfunction "SCLK_N_124") (pintype "passive"))
    )
    (net (code "407") (name "unconnected-(J800-SCLK_N-Pad153)") (class "Default")
      (node (ref "J800") (pin "153") (pinfunction "SCLK_N_153") (pintype "passive"))
    )
    (net (code "408") (name "unconnected-(J800-SCLK_P-Pad69)") (class "Default")
      (node (ref "J800") (pin "69") (pinfunction "SCLK_P_69") (pintype "passive"))
    )
    (net (code "409") (name "unconnected-(J800-SCLK_P-Pad72)") (class "Default")
      (node (ref "J800") (pin "72") (pinfunction "SCLK_P_72") (pintype "passive"))
    )
    (net (code "410") (name "unconnected-(J800-SCLK_P-Pad89)") (class "Default")
      (node (ref "J800") (pin "89") (pinfunction "SCLK_P_89") (pintype "passive"))
    )
    (net (code "411") (name "unconnected-(J800-SCLK_P-Pad115)") (class "Default")
      (node (ref "J800") (pin "115") (pinfunction "SCLK_P_115") (pintype "passive"))
    )
    (net (code "412") (name "unconnected-(J800-SCLK_P-Pad122)") (class "Default")
      (node (ref "J800") (pin "122") (pinfunction "SCLK_P_122") (pintype "passive"))
    )
    (net (code "413") (name "unconnected-(J800-SCLK_P-Pad151)") (class "Default")
      (node (ref "J800") (pin "151") (pinfunction "SCLK_P_151") (pintype "passive"))
    )
    (net (code "414") (name "unconnected-(J800-VIN_IO-Pad76)") (class "Default")
      (node (ref "J800") (pin "76") (pinfunction "VIN_IO_76") (pintype "passive"))
    )
    (net (code "415") (name "unconnected-(J800-VIN_IO-Pad116)") (class "Default")
      (node (ref "J800") (pin "116") (pinfunction "VIN_IO_116") (pintype "passive"))
    )
    (net (code "416") (name "unconnected-(J800-VIN_IO-Pad158)") (class "Default")
      (node (ref "J800") (pin "158") (pinfunction "VIN_IO_158") (pintype "passive"))
    )
    (net (code "417") (name "unconnected-(J800-VMON-Pad8)") (class "Default")
      (node (ref "J800") (pin "8") (pinfunction "VMON_8") (pintype "passive"))
    )
    (net (code "418") (name "unconnected-(J800-VOUT-Pad83)") (class "Default")
      (node (ref "J800") (pin "83") (pinfunction "VOUT_83") (pintype "passive"))
    )
    (net (code "419") (name "unconnected-(J800-VOUT-Pad123)") (class "Default")
      (node (ref "J800") (pin "123") (pinfunction "VOUT_123") (pintype "passive"))
    )
    (net (code "420") (name "unconnected-(J800-VOUT-Pad165)") (class "Default")
      (node (ref "J800") (pin "165") (pinfunction "VOUT_165") (pintype "passive"))
    )
    (net (code "421") (name "unconnected-(J800-VOUT_3V3-Pad96)") (class "Default")
      (node (ref "J800") (pin "96") (pinfunction "VOUT_3V3_96") (pintype "passive"))
    )
    (net (code "422") (name "unconnected-(J800-VOUT_3V3-Pad103)") (class "Default")
      (node (ref "J800") (pin "103") (pinfunction "VOUT_3V3_103") (pintype "passive"))
    )
    (net (code "423") (name "unconnected-(J800-VOUT_3V3-Pad136)") (class "Default")
      (node (ref "J800") (pin "136") (pinfunction "VOUT_3V3_136") (pintype "passive"))
    )
    (net (code "424") (name "unconnected-(J800-VOUT_3V3-Pad143)") (class "Default")
      (node (ref "J800") (pin "143") (pinfunction "VOUT_3V3_143") (pintype "passive"))
    )
  )
)
